# test01.net
KiCad netlist of a schematic drawn in EAGLE
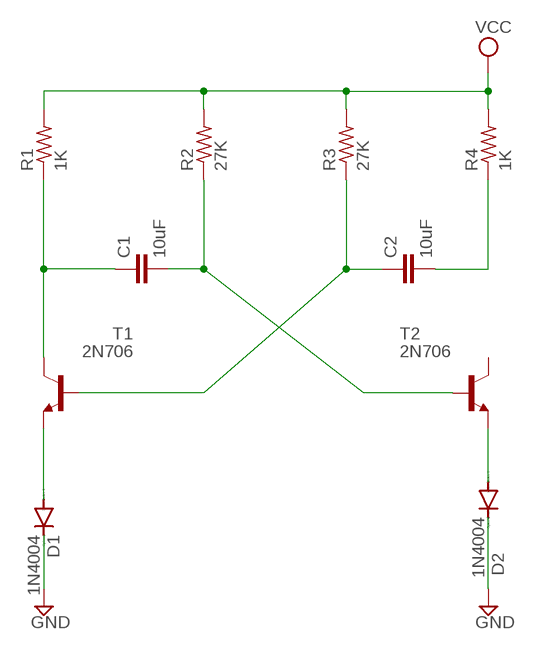
[diagram p0: schematic, sheet 1]

(export (version "E")
  (design (tool "Eeschema 10.0.6"))
  (components
    (comp (ref "C1")
      (value "10uF")
      (footprint "eagle-import:C2.5-3")
      (libsource (lib "eagle-import") (part "C2,5-3"))
    )
    (comp (ref "C2")
      (value "10uF")
      (footprint "eagle-import:C2.5-3")
      (libsource (lib "eagle-import") (part "C2,5-3"))
    )
    (comp (ref "D1")
      (value "1N4004")
      (footprint "eagle-import:DO41-10")
      (libsource (lib "eagle-import") (part "1N4004"))
    )
    (comp (ref "D2")
      (value "1N4004")
      (footprint "eagle-import:DO41-10")
      (libsource (lib "eagle-import") (part "1N4004"))
    )
    (comp (ref "R1")
      (value "1K")
      (footprint "eagle-import:0204_7")
      (libsource (lib "eagle-import") (part "R-US_0204/7"))
    )
    (comp (ref "R2")
      (value "27K")
      (footprint "eagle-import:0204_7")
      (libsource (lib "eagle-import") (part "R-US_0204/7"))
    )
    (comp (ref "R3")
      (value "27K")
      (footprint "eagle-import:0204_7")
      (libsource (lib "eagle-import") (part "R-US_0204/7"))
    )
    (comp (ref "R4")
      (value "1K")
      (footprint "eagle-import:0204_7")
      (libsource (lib "eagle-import") (part "R-US_0204/7"))
    )
    (comp (ref "T1")
      (value "2N706")
      (footprint "eagle-import:TO18")
      (libsource (lib "eagle-import") (part "2N706"))
    )
    (comp (ref "T2")
      (value "2N706")
      (footprint "eagle-import:TO18")
      (libsource (lib "eagle-import") (part "2N706"))
    )
  )
  (nets
    (net (code "1") (name "GND") (class "Default")
      (node (ref "D1") (pin "C") (pinfunction "C_C") (pintype "passive"))
      (node (ref "D2") (pin "C") (pinfunction "C_C") (pintype "passive"))
    )
    (net (code "2") (name "Net-(C2-Pad2)") (class "Default")
      (node (ref "C2") (pin "2") (pinfunction "2_2") (pintype "passive"))
      (node (ref "R4") (pin "1") (pinfunction "1_1") (pintype "passive"))
    )
    (net (code "3") (name "Net-(T1-B)") (class "Default")
      (node (ref "C2") (pin "1") (pinfunction "1_1") (pintype "passive"))
      (node (ref "R3") (pin "1") (pinfunction "1_1") (pintype "passive"))
      (node (ref "T1") (pin "2") (pinfunction "B_2") (pintype "passive"))
    )
    (net (code "4") (name "Net-(T1-C)") (class "Default")
      (node (ref "C1") (pin "1") (pinfunction "1_1") (pintype "passive"))
      (node (ref "R1") (pin "1") (pinfunction "1_1") (pintype "passive"))
      (node (ref "T1") (pin "3") (pinfunction "C_3") (pintype "passive"))
    )
    (net (code "5") (name "Net-(T1-E)") (class "Default")
      (node (ref "D1") (pin "A") (pinfunction "A_A") (pintype "passive"))
      (node (ref "T1") (pin "1") (pinfunction "E_1") (pintype "passive"))
    )
    (net (code "6") (name "Net-(T2-B)") (class "Default")
      (node (ref "C1") (pin "2") (pinfunction "2_2") (pintype "passive"))
      (node (ref "R2") (pin "1") (pinfunction "1_1") (pintype "passive"))
      (node (ref "T2") (pin "2") (pinfunction "B_2") (pintype "passive"))
    )
    (net (code "7") (name "Net-(T2-E)") (class "Default")
      (node (ref "D2") (pin "A") (pinfunction "A_A") (pintype "passive"))
      (node (ref "T2") (pin "1") (pinfunction "E_1") (pintype "passive"))
    )
    (net (code "8") (name "VCC") (class "Default")
      (node (ref "R1") (pin "2") (pinfunction "2_2") (pintype "passive"))
      (node (ref "R2") (pin "2") (pinfunction "2_2") (pintype "passive"))
      (node (ref "R3") (pin "2") (pinfunction "2_2") (pintype "passive"))
      (node (ref "R4") (pin "2") (pinfunction "2_2") (pintype "passive"))
    )
    (net (code "9") (name "unconnected-(T2-C-Pad3)") (class "Default")
      (node (ref "T2") (pin "3") (pinfunction "C_3") (pintype "passive"))
    )
  )
)
